# main_board-v2_2.net
KiCad netlist of a schematic drawn in EAGLE
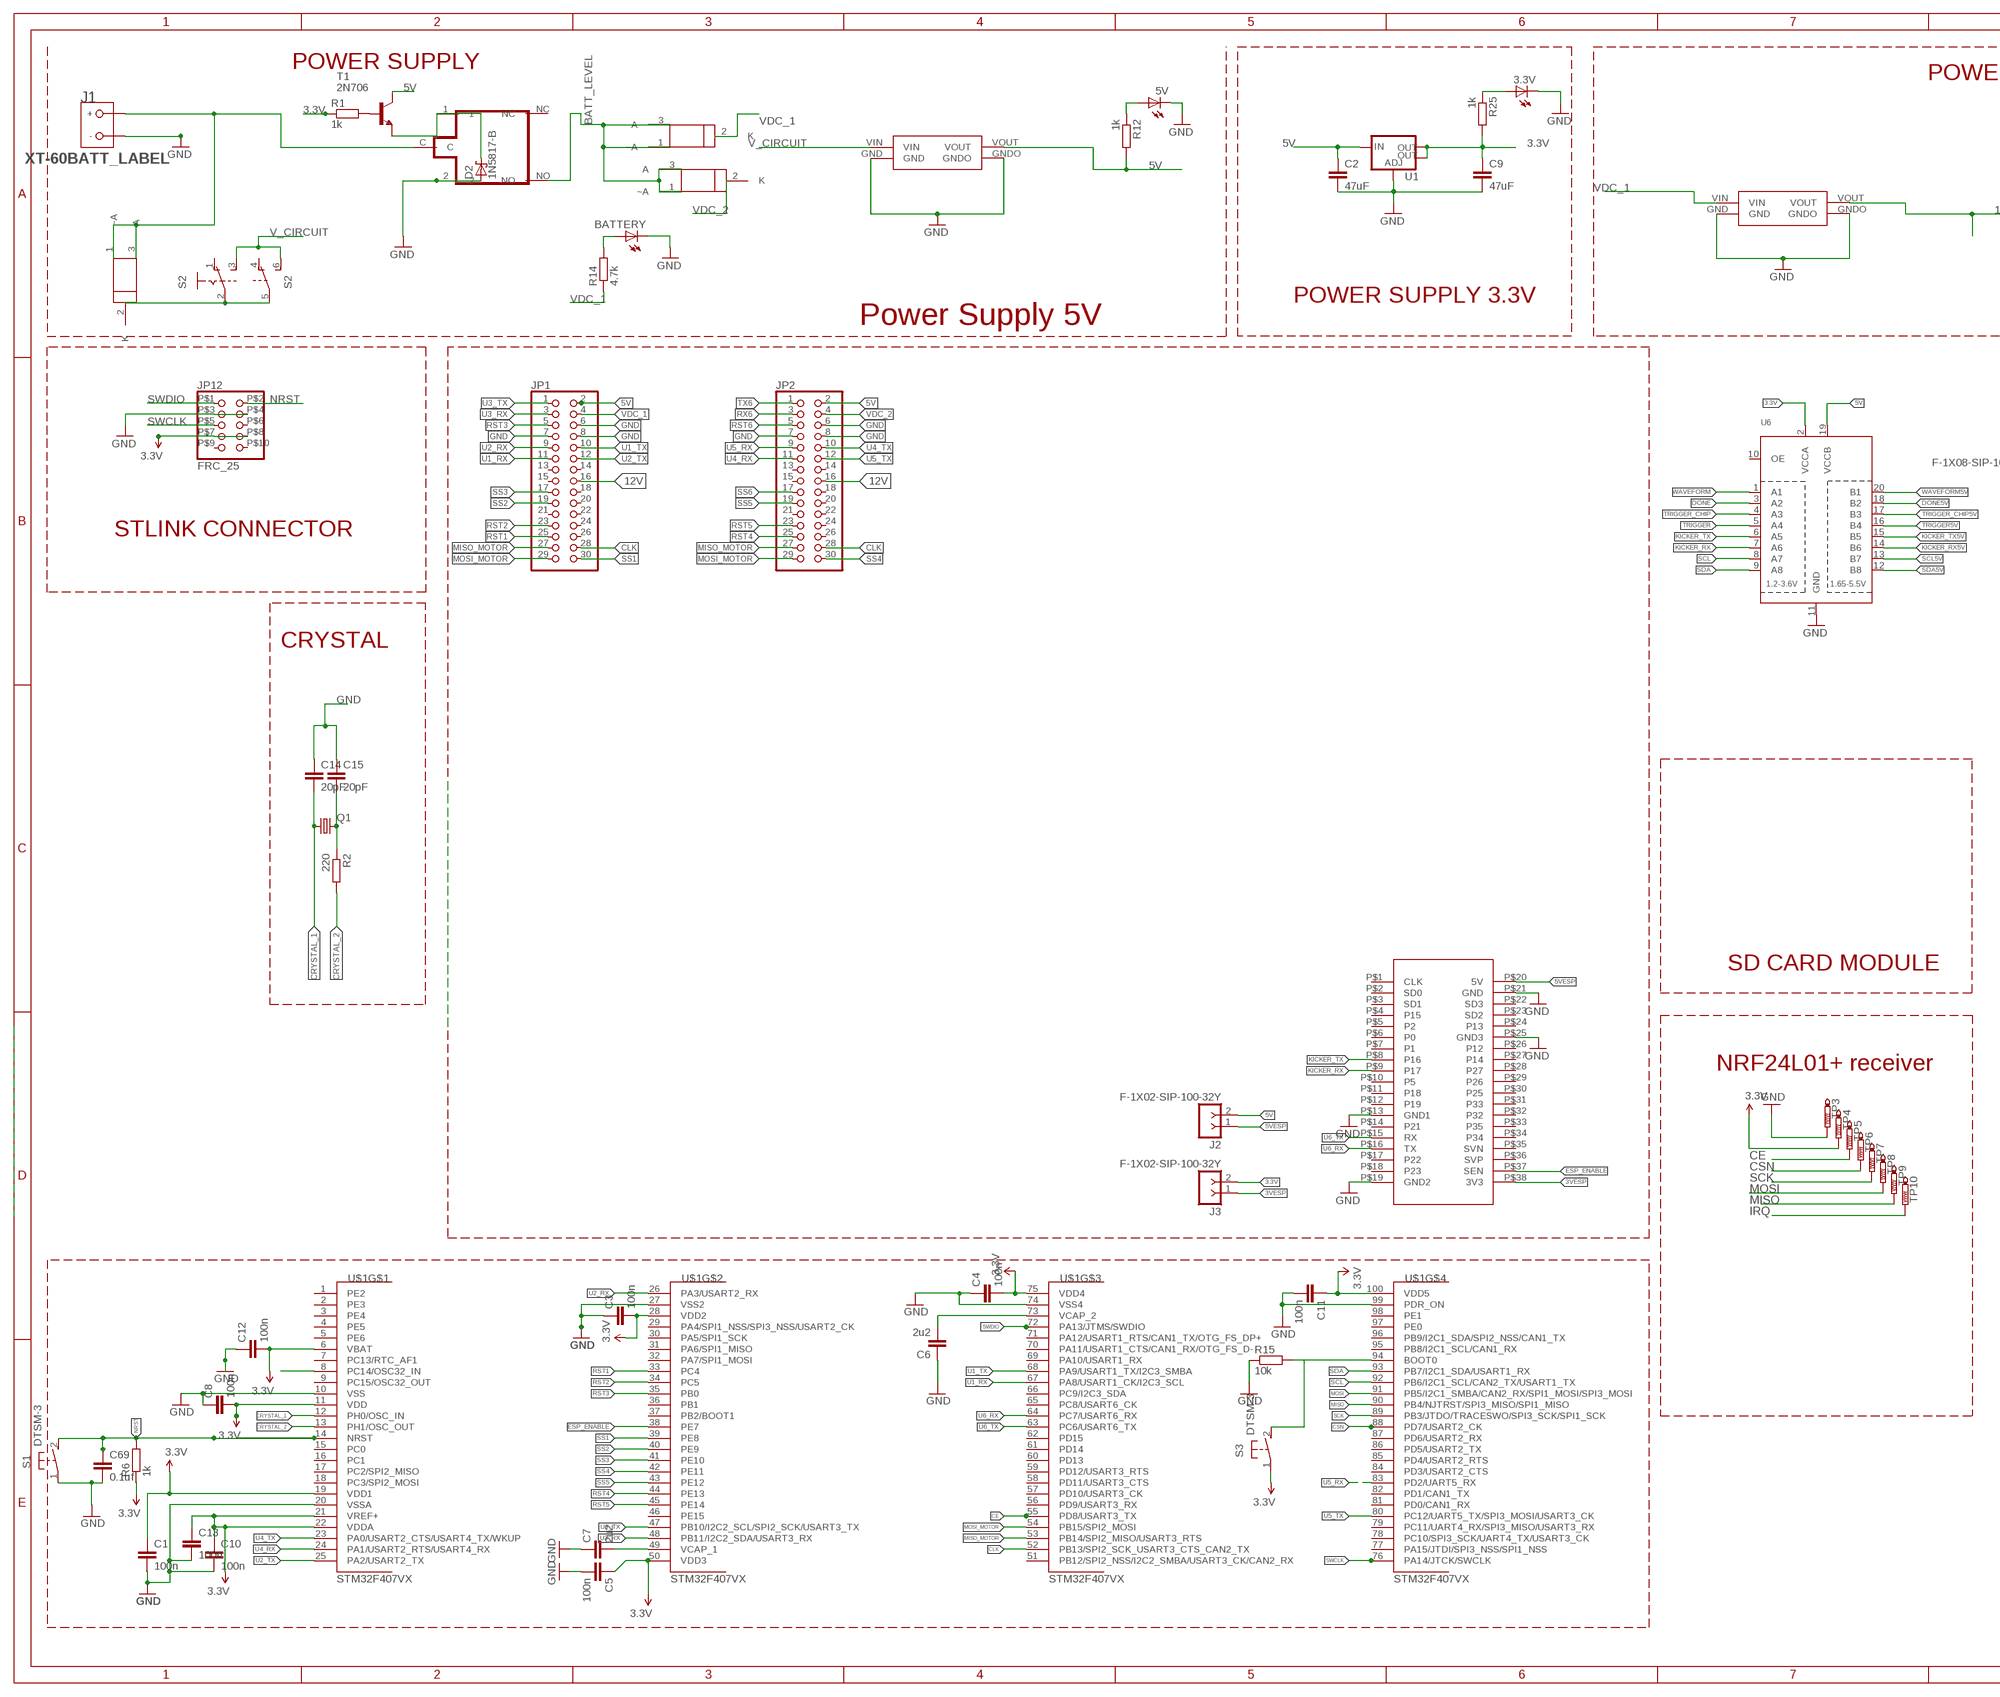
[diagram p0: schematic, sheet 1, part 1 of 2]
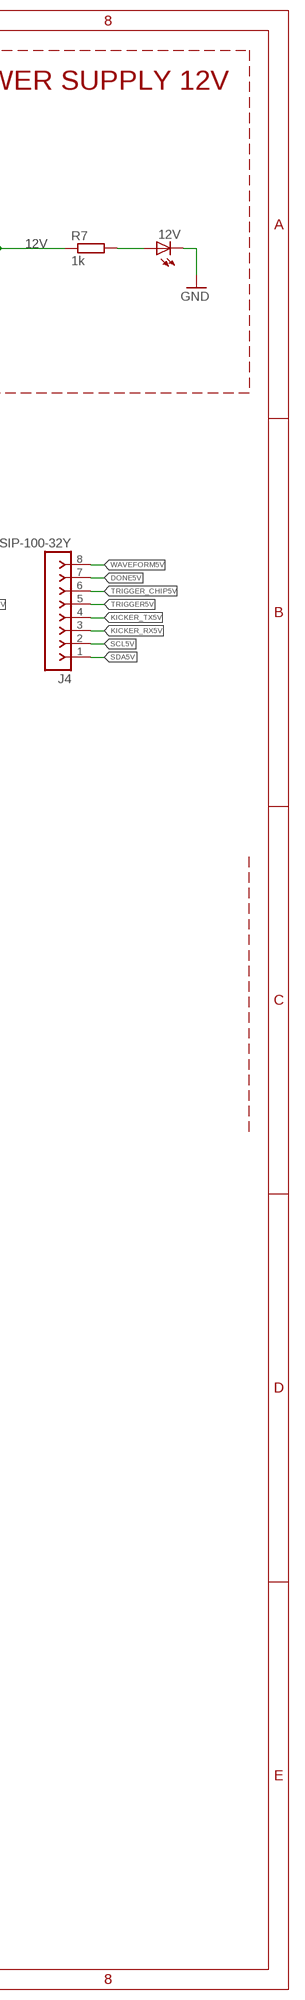
[diagram p1: schematic, sheet 1, part 2 of 2]

(export (version "E")
  (design (tool "Eeschema 10.0.6"))
  (components
    (comp (ref "3.3V")
      (value "LEDCHIPLED_0805")
      (footprint "eagle-import:CHIPLED_0805")
      (libsource (lib "eagle-import") (part "LEDCHIPLED_0805"))
    )
    (comp (ref "5V")
      (value "LEDCHIPLED_0805")
      (footprint "eagle-import:CHIPLED_0805")
      (libsource (lib "eagle-import") (part "LEDCHIPLED_0805"))
    )
    (comp (ref "12V")
      (value "LEDCHIPLED_0805")
      (footprint "eagle-import:CHIPLED_0805")
      (libsource (lib "eagle-import") (part "LEDCHIPLED_0805"))
    )
    (comp (ref "BATTERY")
      (value "LEDCHIPLED_0805")
      (footprint "eagle-import:CHIPLED_0805")
      (libsource (lib "eagle-import") (part "LEDCHIPLED_0805"))
    )
    (comp (ref "C1")
      (value "100n")
      (footprint "eagle-import:C1206")
      (libsource (lib "eagle-import") (part "C-EUC1206"))
    )
    (comp (ref "C2")
      (value "47uF")
      (footprint "eagle-import:C1206")
      (libsource (lib "eagle-import") (part "C-EUC1206"))
    )
    (comp (ref "C3")
      (value "100n")
      (footprint "eagle-import:C1206")
      (libsource (lib "eagle-import") (part "C-EUC1206"))
    )
    (comp (ref "C4")
      (value "100n")
      (footprint "eagle-import:C1206")
      (libsource (lib "eagle-import") (part "C-EUC1206"))
    )
    (comp (ref "C5")
      (value "100n")
      (footprint "eagle-import:C1206")
      (libsource (lib "eagle-import") (part "C-EUC1206"))
    )
    (comp (ref "C6")
      (value "2u2")
      (footprint "eagle-import:C1206")
      (libsource (lib "eagle-import") (part "C-EUC1206"))
    )
    (comp (ref "C7")
      (value "2u2")
      (footprint "eagle-import:C1206")
      (libsource (lib "eagle-import") (part "C-EUC1206"))
    )
    (comp (ref "C8")
      (value "100n")
      (footprint "eagle-import:C1206")
      (libsource (lib "eagle-import") (part "C-EUC1206"))
    )
    (comp (ref "C9")
      (value "47uF")
      (footprint "eagle-import:C1206")
      (libsource (lib "eagle-import") (part "C-EUC1206"))
    )
    (comp (ref "C10")
      (value "100n")
      (footprint "eagle-import:C1206")
      (libsource (lib "eagle-import") (part "C-EUC1206"))
    )
    (comp (ref "C11")
      (value "100n")
      (footprint "eagle-import:C1206")
      (libsource (lib "eagle-import") (part "C-EUC1206"))
    )
    (comp (ref "C12")
      (value "100n")
      (footprint "eagle-import:C1206")
      (libsource (lib "eagle-import") (part "C-EUC1206"))
    )
    (comp (ref "C13")
      (value "100n")
      (footprint "eagle-import:C1206")
      (libsource (lib "eagle-import") (part "C-EUC1206"))
    )
    (comp (ref "C14")
      (value "20pF")
      (footprint "eagle-import:C1206")
      (libsource (lib "eagle-import") (part "C-EUC1206"))
    )
    (comp (ref "C15")
      (value "20pF")
      (footprint "eagle-import:C1206")
      (libsource (lib "eagle-import") (part "C-EUC1206"))
    )
    (comp (ref "C69")
      (value "0.1uf")
      (footprint "eagle-import:C1206")
      (libsource (lib "eagle-import") (part "C-EUC1206"))
    )
    (comp (ref "D2")
      (value "1N5817-B")
      (footprint "eagle-import:DO41-7.6")
      (libsource (lib "eagle-import") (part "1N5817-B"))
    )
    (comp (ref "J1")
      (value "XT-60BATT_LABEL")
      (footprint "eagle-import:XT-60")
      (libsource (lib "eagle-import") (part "XT-60BATT_LABEL"))
    )
    (comp (ref "J2")
      (value "F-1X02-SIP-100-32Y")
      (footprint "eagle-import:SIP-100-02-32Y")
      (libsource (lib "eagle-import") (part "F-1X02-SIP-100-32Y"))
    )
    (comp (ref "J3")
      (value "F-1X02-SIP-100-32Y")
      (footprint "eagle-import:SIP-100-02-32Y")
      (libsource (lib "eagle-import") (part "F-1X02-SIP-100-32Y"))
    )
    (comp (ref "J4")
      (value "F-1X08-SIP-100-32Y")
      (footprint "eagle-import:SIP-100-08-32Y")
      (libsource (lib "eagle-import") (part "F-1X08-SIP-100-32Y"))
    )
    (comp (ref "JP1")
      (value "PINHD-2X15_2.54")
      (footprint "eagle-import:2X15")
      (libsource (lib "eagle-import") (part "PINHD-2X15_2.54"))
    )
    (comp (ref "JP2")
      (value "PINHD-2X15_2.54")
      (footprint "eagle-import:2X15")
      (libsource (lib "eagle-import") (part "PINHD-2X15_2.54"))
    )
    (comp (ref "JP12")
      (value "FRC_25")
      (footprint "eagle-import:FRC2_5")
      (libsource (lib "eagle-import") (part "FRC_25"))
    )
    (comp (ref "Q1")
      (value "CRYSTALHC49U-V")
      (footprint "eagle-import:HC49U-V")
      (libsource (lib "eagle-import") (part "CRYSTALHC49U-V"))
    )
    (comp (ref "R1")
      (value "1k")
      (footprint "eagle-import:R1206")
      (libsource (lib "eagle-import") (part "R-EU_R1206"))
    )
    (comp (ref "R2")
      (value "220")
      (footprint "eagle-import:R1206")
      (libsource (lib "eagle-import") (part "R-EU_R1206"))
    )
    (comp (ref "R6")
      (value "1k")
      (footprint "eagle-import:R1206")
      (libsource (lib "eagle-import") (part "R-EU_R1206"))
    )
    (comp (ref "R7")
      (value "1k")
      (footprint "eagle-import:R1206")
      (libsource (lib "eagle-import") (part "R-EU_R1206"))
    )
    (comp (ref "R12")
      (value "1k")
      (footprint "eagle-import:R1206")
      (libsource (lib "eagle-import") (part "R-EU_R1206"))
    )
    (comp (ref "R14")
      (value "4.7k")
      (footprint "eagle-import:R1206")
      (libsource (lib "eagle-import") (part "R-EU_R1206"))
    )
    (comp (ref "R15")
      (value "10k")
      (footprint "eagle-import:R1206")
      (libsource (lib "eagle-import") (part "R-EU_R1206"))
    )
    (comp (ref "R25")
      (value "1k")
      (footprint "eagle-import:R1206")
      (libsource (lib "eagle-import") (part "R-EU_R1206"))
    )
    (comp (ref "S1")
      (value "DTSM-3")
      (footprint "eagle-import:DTSM-3")
      (libsource (lib "eagle-import") (part "DTSM-3"))
    )
    (comp (ref "S2")
      (value "A68-A31")
      (footprint "eagle-import:A68-A31")
      (libsource (lib "eagle-import") (part "A68-A31"))
    )
    (comp (ref "S3")
      (value "DTSM-3")
      (footprint "eagle-import:DTSM-3")
      (libsource (lib "eagle-import") (part "DTSM-3"))
    )
    (comp (ref "T1")
      (value "2N706")
      (footprint "eagle-import:TO18")
      (libsource (lib "eagle-import") (part "2N706"))
    )
    (comp (ref "TP3")
      (value "PTR1PAD1-13")
      (footprint "eagle-import:P1-13")
      (libsource (lib "eagle-import") (part "PTR1PAD1-13"))
    )
    (comp (ref "TP4")
      (value "PTR1PAD1-13")
      (footprint "eagle-import:P1-13")
      (libsource (lib "eagle-import") (part "PTR1PAD1-13"))
    )
    (comp (ref "TP5")
      (value "PTR1PAD1-13")
      (footprint "eagle-import:P1-13")
      (libsource (lib "eagle-import") (part "PTR1PAD1-13"))
    )
    (comp (ref "TP6")
      (value "PTR1PAD1-13")
      (footprint "eagle-import:P1-13")
      (libsource (lib "eagle-import") (part "PTR1PAD1-13"))
    )
    (comp (ref "TP7")
      (value "PTR1PAD1-13")
      (footprint "eagle-import:P1-13")
      (libsource (lib "eagle-import") (part "PTR1PAD1-13"))
    )
    (comp (ref "TP8")
      (value "PTR1PAD1-13")
      (footprint "eagle-import:P1-13")
      (libsource (lib "eagle-import") (part "PTR1PAD1-13"))
    )
    (comp (ref "TP9")
      (value "PTR1PAD1-13")
      (footprint "eagle-import:P1-13")
      (libsource (lib "eagle-import") (part "PTR1PAD1-13"))
    )
    (comp (ref "TP10")
      (value "PTR1PAD1-13")
      (footprint "eagle-import:P1-13")
      (libsource (lib "eagle-import") (part "PTR1PAD1-13"))
    )
    (comp (ref "U$1")
      (value "STM32F407VX")
      (footprint "eagle-import:LQFP100")
      (libsource (lib "eagle-import") (part "STM32F407VX"))
    )
    (comp (ref "U$2")
      (value "REL")
      (footprint "eagle-import:REL")
      (libsource (lib "eagle-import") (part "REL"))
    )
    (comp (ref "U$3")
      (value "BUCK")
      (footprint "eagle-import:BUCK")
      (libsource (lib "eagle-import") (part "BUCK"))
    )
    (comp (ref "U$4")
      (value "BUCK")
      (footprint "eagle-import:BUCK")
      (libsource (lib "eagle-import") (part "BUCK"))
    )
    (comp (ref "U$6")
      (value "NODEMCU32S")
      (footprint "eagle-import:NODEMCU32")
      (libsource (lib "eagle-import") (part "NODEMCU32S"))
    )
    (comp (ref "U1")
      (value "V_REG_LM1117SOT223")
      (footprint "eagle-import:SOT223")
      (libsource (lib "eagle-import") (part "V_REG_LM1117SOT223"))
    )
    (comp (ref "U2")
      (value "LP38690DT-3.3")
      (footprint "eagle-import:TO228P1042X238-3N")
      (libsource (lib "eagle-import") (part "LP38690DT-3.3"))
    )
    (comp (ref "U3")
      (value "LP38690DT-3.3")
      (footprint "eagle-import:TO228P1042X238-3N")
      (libsource (lib "eagle-import") (part "LP38690DT-3.3"))
    )
    (comp (ref "U4")
      (value "LP38690DT-3.3")
      (footprint "eagle-import:TO228P1042X238-3N")
      (libsource (lib "eagle-import") (part "LP38690DT-3.3"))
    )
    (comp (ref "U6")
      (value "TXB0108PWR")
      (footprint "eagle-import:TSSOP20")
      (libsource (lib "eagle-import") (part "TXB0108PWR"))
    )
  )
  (nets
    (net (code "1") (name "/BATT_LEVEL") (class "Default")
      (node (ref "U$2") (pin "NO") (pinfunction "NO_NO") (pintype "bidirectional"))
      (node (ref "U2") (pin "1") (pinfunction "~{A}_1") (pintype "bidirectional"))
      (node (ref "U2") (pin "3") (pinfunction "A_3") (pintype "bidirectional"))
      (node (ref "U4") (pin "1") (pinfunction "~{A}_1") (pintype "bidirectional"))
      (node (ref "U4") (pin "3") (pinfunction "A_3") (pintype "bidirectional"))
    )
    (net (code "2") (name "/IRQ") (class "Default")
      (node (ref "TP10") (pin "TP") (pinfunction "TP_TP") (pintype "input"))
    )
    (net (code "3") (name "/V_CIRCUIT") (class "Default")
      (node (ref "S2") (pin "3") (pinfunction "S_3") (pintype "passive"))
      (node (ref "S2") (pin "6") (pinfunction "S_6") (pintype "passive"))
      (node (ref "U$3") (pin "VIN") (pinfunction "VIN_VIN") (pintype "bidirectional"))
    )
    (net (code "4") (name "3.3V") (class "Default")
      (node (ref "C1") (pin "1") (pinfunction "1_1") (pintype "passive"))
      (node (ref "C10") (pin "1") (pinfunction "1_1") (pintype "passive"))
      (node (ref "C11") (pin "1") (pinfunction "1_1") (pintype "passive"))
      (node (ref "C12") (pin "2") (pinfunction "2_2") (pintype "passive"))
      (node (ref "C13") (pin "1") (pinfunction "1_1") (pintype "passive"))
      (node (ref "C3") (pin "2") (pinfunction "2_2") (pintype "passive"))
      (node (ref "C4") (pin "2") (pinfunction "2_2") (pintype "passive"))
      (node (ref "C5") (pin "1") (pinfunction "1_1") (pintype "passive"))
      (node (ref "C8") (pin "2") (pinfunction "2_2") (pintype "passive"))
      (node (ref "C9") (pin "1") (pinfunction "1_1") (pintype "passive"))
      (node (ref "J3") (pin "2") (pinfunction "2_2") (pintype "passive"))
      (node (ref "JP12") (pin "P$7") (pinfunction "7_P$7") (pintype "passive"))
      (node (ref "JP12") (pin "P$8") (pinfunction "8_P$8") (pintype "passive"))
      (node (ref "R1") (pin "1") (pinfunction "1_1") (pintype "passive"))
      (node (ref "R25") (pin "2") (pinfunction "2_2") (pintype "passive"))
      (node (ref "R6") (pin "1") (pinfunction "1_1") (pintype "passive"))
      (node (ref "S3") (pin "1") (pinfunction "1_1") (pintype "passive"))
      (node (ref "TP4") (pin "TP") (pinfunction "TP_TP") (pintype "input"))
      (node (ref "U$1") (pin "100") (pinfunction "VDD5_100") (pintype "bidirectional"))
      (node (ref "U$1") (pin "11") (pinfunction "VDD_11") (pintype "bidirectional"))
      (node (ref "U$1") (pin "19") (pinfunction "VDD1_19") (pintype "bidirectional"))
      (node (ref "U$1") (pin "21") (pinfunction "VREF+_21") (pintype "bidirectional"))
      (node (ref "U$1") (pin "22") (pinfunction "VDDA_22") (pintype "bidirectional"))
      (node (ref "U$1") (pin "28") (pinfunction "VDD2_28") (pintype "bidirectional"))
      (node (ref "U$1") (pin "50") (pinfunction "VDD3_50") (pintype "bidirectional"))
      (node (ref "U$1") (pin "6") (pinfunction "VBAT_6") (pintype "bidirectional"))
      (node (ref "U$1") (pin "75") (pinfunction "VDD4_75") (pintype "bidirectional"))
      (node (ref "U1") (pin "2") (pinfunction "OUT_2") (pintype "output"))
      (node (ref "U1") (pin "4") (pinfunction "OUT_4") (pintype "output"))
      (node (ref "U6") (pin "2") (pinfunction "VCCA_2") (pintype "bidirectional"))
    )
    (net (code "5") (name "3VESP") (class "Default")
      (node (ref "J3") (pin "1") (pinfunction "1_1") (pintype "passive"))
      (node (ref "U$6") (pin "P$38") (pinfunction "3V3_P$38") (pintype "bidirectional"))
    )
    (net (code "6") (name "5V") (class "Default")
      (node (ref "C2") (pin "1") (pinfunction "1_1") (pintype "passive"))
      (node (ref "J2") (pin "2") (pinfunction "2_2") (pintype "passive"))
      (node (ref "JP1") (pin "2") (pinfunction "2_2") (pintype "passive"))
      (node (ref "JP2") (pin "2") (pinfunction "2_2") (pintype "passive"))
      (node (ref "R12") (pin "2") (pinfunction "2_2") (pintype "passive"))
      (node (ref "T1") (pin "3") (pinfunction "C_3") (pintype "passive"))
      (node (ref "U$3") (pin "VOUT") (pinfunction "VOUT_VOUT") (pintype "bidirectional"))
      (node (ref "U1") (pin "3") (pinfunction "IN_3") (pintype "input"))
      (node (ref "U6") (pin "19") (pinfunction "VCCB_19") (pintype "bidirectional"))
    )
    (net (code "7") (name "5VESP") (class "Default")
      (node (ref "J2") (pin "1") (pinfunction "1_1") (pintype "passive"))
      (node (ref "U$6") (pin "P$20") (pinfunction "5V_P$20") (pintype "bidirectional"))
    )
    (net (code "8") (name "12V") (class "Default")
      (node (ref "JP1") (pin "16") (pinfunction "16_16") (pintype "passive"))
      (node (ref "JP2") (pin "16") (pinfunction "16_16") (pintype "passive"))
      (node (ref "R7") (pin "1") (pinfunction "1_1") (pintype "passive"))
      (node (ref "U$4") (pin "VOUT") (pinfunction "VOUT_VOUT") (pintype "bidirectional"))
    )
    (net (code "9") (name "CE") (class "Default")
      (node (ref "TP5") (pin "TP") (pinfunction "TP_TP") (pintype "input"))
      (node (ref "U$1") (pin "55") (pinfunction "PD8/USART3_TX_55") (pintype "bidirectional"))
    )
    (net (code "10") (name "CLK") (class "Default")
      (node (ref "JP1") (pin "28") (pinfunction "28_28") (pintype "passive"))
      (node (ref "JP2") (pin "28") (pinfunction "28_28") (pintype "passive"))
      (node (ref "U$1") (pin "52") (pinfunction "PB13/SPI2_SCK_USART3_CTS_CAN2_TX_52") (pintype "bidirectional"))
    )
    (net (code "11") (name "CRYSTAL_1") (class "Default")
      (node (ref "C14") (pin "2") (pinfunction "2_2") (pintype "passive"))
      (node (ref "Q1") (pin "1") (pinfunction "1_1") (pintype "passive"))
      (node (ref "U$1") (pin "12") (pinfunction "PH0/OSC_IN_12") (pintype "bidirectional"))
    )
    (net (code "12") (name "CRYSTAL_2") (class "Default")
      (node (ref "R2") (pin "2") (pinfunction "2_2") (pintype "passive"))
      (node (ref "U$1") (pin "13") (pinfunction "PH1/OSC_OUT_13") (pintype "bidirectional"))
    )
    (net (code "13") (name "CSN") (class "Default")
      (node (ref "TP6") (pin "TP") (pinfunction "TP_TP") (pintype "input"))
      (node (ref "U$1") (pin "88") (pinfunction "PD7/USART2_CK_88") (pintype "bidirectional"))
    )
    (net (code "14") (name "DONE") (class "Default")
      (node (ref "U6") (pin "3") (pinfunction "A2_3") (pintype "bidirectional"))
    )
    (net (code "15") (name "DONE5V") (class "Default")
      (node (ref "J4") (pin "7") (pinfunction "7_7") (pintype "passive"))
      (node (ref "U6") (pin "18") (pinfunction "B2_18") (pintype "bidirectional"))
    )
    (net (code "16") (name "ESP_ENABLE") (class "Default")
      (node (ref "U$1") (pin "38") (pinfunction "PE7_38") (pintype "bidirectional"))
      (node (ref "U$6") (pin "P$37") (pinfunction "SEN_P$37") (pintype "bidirectional"))
    )
    (net (code "17") (name "GND") (class "Default")
      (node (ref "12V") (pin "C") (pinfunction "C_C") (pintype "passive"))
      (node (ref "3.3V") (pin "C") (pinfunction "C_C") (pintype "passive"))
      (node (ref "5V") (pin "C") (pinfunction "C_C") (pintype "passive"))
      (node (ref "BATTERY") (pin "C") (pinfunction "C_C") (pintype "passive"))
      (node (ref "C1") (pin "2") (pinfunction "2_2") (pintype "passive"))
      (node (ref "C10") (pin "2") (pinfunction "2_2") (pintype "passive"))
      (node (ref "C11") (pin "2") (pinfunction "2_2") (pintype "passive"))
      (node (ref "C12") (pin "1") (pinfunction "1_1") (pintype "passive"))
      (node (ref "C13") (pin "2") (pinfunction "2_2") (pintype "passive"))
      (node (ref "C14") (pin "1") (pinfunction "1_1") (pintype "passive"))
      (node (ref "C15") (pin "1") (pinfunction "1_1") (pintype "passive"))
      (node (ref "C2") (pin "2") (pinfunction "2_2") (pintype "passive"))
      (node (ref "C3") (pin "1") (pinfunction "1_1") (pintype "passive"))
      (node (ref "C4") (pin "1") (pinfunction "1_1") (pintype "passive"))
      (node (ref "C5") (pin "2") (pinfunction "2_2") (pintype "passive"))
      (node (ref "C6") (pin "1") (pinfunction "1_1") (pintype "passive"))
      (node (ref "C69") (pin "2") (pinfunction "2_2") (pintype "passive"))
      (node (ref "C7") (pin "1") (pinfunction "1_1") (pintype "passive"))
      (node (ref "C8") (pin "1") (pinfunction "1_1") (pintype "passive"))
      (node (ref "C9") (pin "2") (pinfunction "2_2") (pintype "passive"))
      (node (ref "D2") (pin "A") (pinfunction "A_A") (pintype "passive"))
      (node (ref "J1") (pin "GND") (pinfunction "-_GND") (pintype "passive"))
      (node (ref "JP1") (pin "6") (pinfunction "6_6") (pintype "passive"))
      (node (ref "JP1") (pin "7") (pinfunction "7_7") (pintype "passive"))
      (node (ref "JP1") (pin "8") (pinfunction "8_8") (pintype "passive"))
      (node (ref "JP12") (pin "P$3") (pinfunction "3_P$3") (pintype "passive"))
      (node (ref "JP12") (pin "P$4") (pinfunction "4_P$4") (pintype "passive"))
      (node (ref "JP2") (pin "6") (pinfunction "6_6") (pintype "passive"))
      (node (ref "JP2") (pin "7") (pinfunction "7_7") (pintype "passive"))
      (node (ref "JP2") (pin "8") (pinfunction "8_8") (pintype "passive"))
      (node (ref "R15") (pin "1") (pinfunction "1_1") (pintype "passive"))
      (node (ref "S1") (pin "1") (pinfunction "1_1") (pintype "passive"))
      (node (ref "TP3") (pin "TP") (pinfunction "TP_TP") (pintype "input"))
      (node (ref "U$1") (pin "10") (pinfunction "VSS_10") (pintype "bidirectional"))
      (node (ref "U$1") (pin "20") (pinfunction "VSSA_20") (pintype "bidirectional"))
      (node (ref "U$1") (pin "27") (pinfunction "VSS2_27") (pintype "bidirectional"))
      (node (ref "U$1") (pin "74") (pinfunction "VSS4_74") (pintype "bidirectional"))
      (node (ref "U$1") (pin "99") (pinfunction "PDR_ON_99") (pintype "bidirectional"))
      (node (ref "U$2") (pin "2") (pinfunction "2_2") (pintype "bidirectional"))
      (node (ref "U$3") (pin "GND") (pinfunction "GND_GND") (pintype "bidirectional"))
      (node (ref "U$3") (pin "GNDO") (pinfunction "GNDO_GNDO") (pintype "bidirectional"))
      (node (ref "U$4") (pin "GND") (pinfunction "GND_GND") (pintype "bidirectional"))
      (node (ref "U$4") (pin "GNDO") (pinfunction "GNDO_GNDO") (pintype "bidirectional"))
      (node (ref "U$6") (pin "P$13") (pinfunction "GND1_P$13") (pintype "bidirectional"))
      (node (ref "U$6") (pin "P$19") (pinfunction "GND2_P$19") (pintype "bidirectional"))
      (node (ref "U$6") (pin "P$21") (pinfunction "GND_P$21") (pintype "bidirectional"))
      (node (ref "U$6") (pin "P$25") (pinfunction "GND3_P$25") (pintype "bidirectional"))
      (node (ref "U1") (pin "1") (pinfunction "ADJ_1") (pintype "input"))
      (node (ref "U6") (pin "11") (pinfunction "GND_11") (pintype "bidirectional"))
    )
    (net (code "18") (name "KICKER_RX") (class "Default")
      (node (ref "U$6") (pin "P$9") (pinfunction "P17_P$9") (pintype "bidirectional"))
      (node (ref "U6") (pin "7") (pinfunction "A6_7") (pintype "bidirectional"))
    )
    (net (code "19") (name "KICKER_RX5V") (class "Default")
      (node (ref "J4") (pin "3") (pinfunction "3_3") (pintype "passive"))
      (node (ref "U6") (pin "14") (pinfunction "B6_14") (pintype "bidirectional"))
    )
    (net (code "20") (name "KICKER_TX") (class "Default")
      (node (ref "U$6") (pin "P$8") (pinfunction "P16_P$8") (pintype "bidirectional"))
      (node (ref "U6") (pin "6") (pinfunction "A5_6") (pintype "bidirectional"))
    )
    (net (code "21") (name "KICKER_TX5V") (class "Default")
      (node (ref "J4") (pin "4") (pinfunction "4_4") (pintype "passive"))
      (node (ref "U6") (pin "15") (pinfunction "B5_15") (pintype "bidirectional"))
    )
    (net (code "22") (name "MISO") (class "Default")
      (node (ref "TP9") (pin "TP") (pinfunction "TP_TP") (pintype "input"))
      (node (ref "U$1") (pin "90") (pinfunction "PB4/NJTRST/SPI3_MISO/SPI1_MISO_90") (pintype "bidirectional"))
    )
    (net (code "23") (name "MISO_MOTOR") (class "Default")
      (node (ref "JP1") (pin "27") (pinfunction "27_27") (pintype "passive"))
      (node (ref "JP2") (pin "27") (pinfunction "27_27") (pintype "passive"))
      (node (ref "U$1") (pin "53") (pinfunction "PB14/SPI2_MISO/USART3_RTS_53") (pintype "bidirectional"))
    )
    (net (code "24") (name "MOSI") (class "Default")
      (node (ref "TP8") (pin "TP") (pinfunction "TP_TP") (pintype "input"))
      (node (ref "U$1") (pin "91") (pinfunction "PB5/I2C1_SMBA/CAN2_RX/SPI1_MOSI/SPI3_MOSI_91") (pintype "bidirectional"))
    )
    (net (code "25") (name "MOSI_MOTOR") (class "Default")
      (node (ref "JP1") (pin "29") (pinfunction "29_29") (pintype "passive"))
      (node (ref "JP2") (pin "29") (pinfunction "29_29") (pintype "passive"))
      (node (ref "U$1") (pin "54") (pinfunction "PB15/SPI2_MOSI_54") (pintype "bidirectional"))
    )
    (net (code "26") (name "NRST") (class "Default")
      (node (ref "C69") (pin "1") (pinfunction "1_1") (pintype "passive"))
      (node (ref "JP12") (pin "P$2") (pinfunction "2_P$2") (pintype "passive"))
      (node (ref "R6") (pin "2") (pinfunction "2_2") (pintype "passive"))
      (node (ref "S1") (pin "2") (pinfunction "2_2") (pintype "passive"))
      (node (ref "U$1") (pin "14") (pinfunction "NRST_14") (pintype "bidirectional"))
    )
    (net (code "27") (name "Net-(3.3V-PadA)") (class "Default")
      (node (ref "3.3V") (pin "A") (pinfunction "A_A") (pintype "passive"))
      (node (ref "R25") (pin "1") (pinfunction "1_1") (pintype "passive"))
    )
    (net (code "28") (name "Net-(5V-PadA)") (class "Default")
      (node (ref "5V") (pin "A") (pinfunction "A_A") (pintype "passive"))
      (node (ref "R12") (pin "1") (pinfunction "1_1") (pintype "passive"))
    )
    (net (code "29") (name "Net-(12V-PadA)") (class "Default")
      (node (ref "12V") (pin "A") (pinfunction "A_A") (pintype "passive"))
      (node (ref "R7") (pin "2") (pinfunction "2_2") (pintype "passive"))
    )
    (net (code "30") (name "Net-(BATTERY-PadA)") (class "Default")
      (node (ref "BATTERY") (pin "A") (pinfunction "A_A") (pintype "passive"))
      (node (ref "R14") (pin "2") (pinfunction "2_2") (pintype "passive"))
    )
    (net (code "31") (name "Net-(C15-Pad2)") (class "Default")
      (node (ref "C15") (pin "2") (pinfunction "2_2") (pintype "passive"))
      (node (ref "Q1") (pin "2") (pinfunction "2_2") (pintype "passive"))
      (node (ref "R2") (pin "1") (pinfunction "1_1") (pintype "passive"))
    )
    (net (code "32") (name "Net-(J1-+)") (class "Default")
      (node (ref "J1") (pin "BATT") (pinfunction "+_BATT") (pintype "passive"))
      (node (ref "U$2") (pin "C") (pinfunction "C_C") (pintype "bidirectional"))
      (node (ref "U3") (pin "1") (pinfunction "~{A}_1") (pintype "bidirectional"))
      (node (ref "U3") (pin "3") (pinfunction "A_3") (pintype "bidirectional"))
    )
    (net (code "33") (name "Net-(S2A-P)") (class "Default")
      (node (ref "S2") (pin "2") (pinfunction "P_2") (pintype "passive"))
      (node (ref "S2") (pin "5") (pinfunction "P_5") (pintype "passive"))
      (node (ref "U3") (pin "2") (pinfunction "K_2") (pintype "bidirectional"))
    )
    (net (code "34") (name "Net-(T1-B)") (class "Default")
      (node (ref "R1") (pin "2") (pinfunction "2_2") (pintype "passive"))
      (node (ref "T1") (pin "2") (pinfunction "B_2") (pintype "passive"))
    )
    (net (code "35") (name "Net-(T1-E)") (class "Default")
      (node (ref "D2") (pin "C") (pinfunction "C_C") (pintype "passive"))
      (node (ref "T1") (pin "1") (pinfunction "E_1") (pintype "passive"))
      (node (ref "U$2") (pin "1") (pinfunction "1_1") (pintype "bidirectional"))
    )
    (net (code "36") (name "Net-(U$1B-VCAP_1)") (class "Default")
      (node (ref "C7") (pin "2") (pinfunction "2_2") (pintype "passive"))
      (node (ref "U$1") (pin "49") (pinfunction "VCAP_1_49") (pintype "bidirectional"))
    )
    (net (code "37") (name "Net-(U$1C-VCAP_2)") (class "Default")
      (node (ref "C6") (pin "2") (pinfunction "2_2") (pintype "passive"))
      (node (ref "U$1") (pin "73") (pinfunction "VCAP_2_73") (pintype "bidirectional"))
    )
    (net (code "38") (name "Net-(U$1D-BOOT0)") (class "Default")
      (node (ref "R15") (pin "2") (pinfunction "2_2") (pintype "passive"))
      (node (ref "S3") (pin "2") (pinfunction "2_2") (pintype "passive"))
      (node (ref "U$1") (pin "94") (pinfunction "BOOT0_94") (pintype "bidirectional"))
    )
    (net (code "39") (name "RST1") (class "Default")
      (node (ref "JP1") (pin "25") (pinfunction "25_25") (pintype "passive"))
      (node (ref "U$1") (pin "33") (pinfunction "PC4_33") (pintype "bidirectional"))
    )
    (net (code "40") (name "RST2") (class "Default")
      (node (ref "JP1") (pin "23") (pinfunction "23_23") (pintype "passive"))
      (node (ref "U$1") (pin "34") (pinfunction "PC5_34") (pintype "bidirectional"))
    )
    (net (code "41") (name "RST3") (class "Default")
      (node (ref "JP1") (pin "5") (pinfunction "5_5") (pintype "passive"))
      (node (ref "U$1") (pin "35") (pinfunction "PB0_35") (pintype "bidirectional"))
    )
    (net (code "42") (name "RST4") (class "Default")
      (node (ref "JP2") (pin "25") (pinfunction "25_25") (pintype "passive"))
      (node (ref "U$1") (pin "44") (pinfunction "PE13_44") (pintype "bidirectional"))
    )
    (net (code "43") (name "RST5") (class "Default")
      (node (ref "JP2") (pin "23") (pinfunction "23_23") (pintype "passive"))
      (node (ref "U$1") (pin "45") (pinfunction "PE14_45") (pintype "bidirectional"))
    )
    (net (code "44") (name "RST6") (class "Default")
      (node (ref "JP2") (pin "5") (pinfunction "5_5") (pintype "passive"))
    )
    (net (code "45") (name "RX6") (class "Default")
      (node (ref "JP2") (pin "3") (pinfunction "3_3") (pintype "passive"))
    )
    (net (code "46") (name "SCK") (class "Default")
      (node (ref "TP7") (pin "TP") (pinfunction "TP_TP") (pintype "input"))
      (node (ref "U$1") (pin "89") (pinfunction "PB3/JTDO/TRACESWO/SPI3_SCK/SPI1_SCK_89") (pintype "bidirectional"))
    )
    (net (code "47") (name "SCL") (class "Default")
      (node (ref "U$1") (pin "92") (pinfunction "PB6/I2C1_SCL/CAN2_TX/USART1_TX_92") (pintype "bidirectional"))
      (node (ref "U6") (pin "8") (pinfunction "A7_8") (pintype "bidirectional"))
    )
    (net (code "48") (name "SCL5V") (class "Default")
      (node (ref "J4") (pin "2") (pinfunction "2_2") (pintype "passive"))
      (node (ref "U6") (pin "13") (pinfunction "B7_13") (pintype "bidirectional"))
    )
    (net (code "49") (name "SDA") (class "Default")
      (node (ref "U$1") (pin "93") (pinfunction "PB7/I2C1_SDA/USART1_RX_93") (pintype "bidirectional"))
      (node (ref "U6") (pin "9") (pinfunction "A8_9") (pintype "bidirectional"))
    )
    (net (code "50") (name "SDA5V") (class "Default")
      (node (ref "J4") (pin "1") (pinfunction "1_1") (pintype "passive"))
      (node (ref "U6") (pin "12") (pinfunction "B8_12") (pintype "bidirectional"))
    )
    (net (code "51") (name "SS1") (class "Default")
      (node (ref "JP1") (pin "30") (pinfunction "30_30") (pintype "passive"))
      (node (ref "U$1") (pin "39") (pinfunction "PE8_39") (pintype "bidirectional"))
    )
    (net (code "52") (name "SS2") (class "Default")
      (node (ref "JP1") (pin "19") (pinfunction "19_19") (pintype "passive"))
      (node (ref "U$1") (pin "40") (pinfunction "PE9_40") (pintype "bidirectional"))
    )
    (net (code "53") (name "SS3") (class "Default")
      (node (ref "JP1") (pin "17") (pinfunction "17_17") (pintype "passive"))
      (node (ref "U$1") (pin "41") (pinfunction "PE10_41") (pintype "bidirectional"))
    )
    (net (code "54") (name "SS4") (class "Default")
      (node (ref "JP2") (pin "30") (pinfunction "30_30") (pintype "passive"))
      (node (ref "U$1") (pin "42") (pinfunction "PE11_42") (pintype "bidirectional"))
    )
    (net (code "55") (name "SS5") (class "Default")
      (node (ref "JP2") (pin "19") (pinfunction "19_19") (pintype "passive"))
      (node (ref "U$1") (pin "43") (pinfunction "PE12_43") (pintype "bidirectional"))
    )
    (net (code "56") (name "SS6") (class "Default")
      (node (ref "JP2") (pin "17") (pinfunction "17_17") (pintype "passive"))
    )
    (net (code "57") (name "SWCLK") (class "Default")
      (node (ref "JP12") (pin "P$5") (pinfunction "5_P$5") (pintype "passive"))
      (node (ref "U$1") (pin "76") (pinfunction "PA14/JTCK/SWCLK_76") (pintype "bidirectional"))
    )
    (net (code "58") (name "SWDIO") (class "Default")
      (node (ref "JP12") (pin "P$1") (pinfunction "1_P$1") (pintype "passive"))
      (node (ref "U$1") (pin "72") (pinfunction "PA13/JTMS/SWDIO_72") (pintype "bidirectional"))
    )
    (net (code "59") (name "TRIGGER") (class "Default")
      (node (ref "U6") (pin "5") (pinfunction "A4_5") (pintype "bidirectional"))
    )
    (net (code "60") (name "TRIGGER5V") (class "Default")
      (node (ref "J4") (pin "5") (pinfunction "5_5") (pintype "passive"))
      (node (ref "U6") (pin "16") (pinfunction "B4_16") (pintype "bidirectional"))
    )
    (net (code "61") (name "TRIGGER_CHIP") (class "Default")
      (node (ref "U6") (pin "4") (pinfunction "A3_4") (pintype "bidirectional"))
    )
    (net (code "62") (name "TRIGGER_CHIP5V") (class "Default")
      (node (ref "J4") (pin "6") (pinfunction "6_6") (pintype "passive"))
      (node (ref "U6") (pin "17") (pinfunction "B3_17") (pintype "bidirectional"))
    )
    (net (code "63") (name "TX6") (class "Default")
      (node (ref "JP2") (pin "1") (pinfunction "1_1") (pintype "passive"))
    )
    (net (code "64") (name "U1_RX") (class "Default")
      (node (ref "JP1") (pin "11") (pinfunction "11_11") (pintype "passive"))
      (node (ref "U$1") (pin "67") (pinfunction "PA8/USART1_CK/I2C3_SCL_67") (pintype "bidirectional"))
    )
    (net (code "65") (name "U1_TX") (class "Default")
      (node (ref "JP1") (pin "10") (pinfunction "10_10") (pintype "passive"))
      (node (ref "U$1") (pin "68") (pinfunction "PA9/USART1_TX/I2C3_SMBA_68") (pintype "bidirectional"))
    )
    (net (code "66") (name "U2_RX") (class "Default")
      (node (ref "JP1") (pin "9") (pinfunction "9_9") (pintype "passive"))
      (node (ref "U$1") (pin "26") (pinfunction "PA3/USART2_RX_26") (pintype "bidirectional"))
    )
    (net (code "67") (name "U2_TX") (class "Default")
      (node (ref "JP1") (pin "12") (pinfunction "12_12") (pintype "passive"))
      (node (ref "U$1") (pin "25") (pinfunction "PA2/USART2_TX_25") (pintype "bidirectional"))
    )
    (net (code "68") (name "U3_RX") (class "Default")
      (node (ref "JP1") (pin "3") (pinfunction "3_3") (pintype "passive"))
      (node (ref "U$1") (pin "48") (pinfunction "PB11/I2C2_SDA/USART3_RX_48") (pintype "bidirectional"))
    )
    (net (code "69") (name "U3_TX") (class "Default")
      (node (ref "JP1") (pin "1") (pinfunction "1_1") (pintype "passive"))
      (node (ref "U$1") (pin "47") (pinfunction "PB10/I2C2_SCL/SPI2_SCK/USART3_TX_47") (pintype "bidirectional"))
    )
    (net (code "70") (name "U4_RX") (class "Default")
      (node (ref "JP2") (pin "11") (pinfunction "11_11") (pintype "passive"))
      (node (ref "U$1") (pin "24") (pinfunction "PA1/USART2_RTS/USART4_RX_24") (pintype "bidirectional"))
    )
    (net (code "71") (name "U4_TX") (class "Default")
      (node (ref "JP2") (pin "10") (pinfunction "10_10") (pintype "passive"))
      (node (ref "U$1") (pin "23") (pinfunction "PA0/USART2_CTS/USART4_TX/WKUP_23") (pintype "bidirectional"))
    )
    (net (code "72") (name "U5_RX") (class "Default")
      (node (ref "JP2") (pin "9") (pinfunction "9_9") (pintype "passive"))
      (node (ref "U$1") (pin "83") (pinfunction "PD2/UART5_RX_83") (pintype "bidirectional"))
    )
    (net (code "73") (name "U5_TX") (class "Default")
      (node (ref "JP2") (pin "12") (pinfunction "12_12") (pintype "passive"))
      (node (ref "U$1") (pin "80") (pinfunction "PC12/UART5_TX/SPI3_MOSI/USART3_CK_80") (pintype "bidirectional"))
    )
    (net (code "74") (name "U6_RX") (class "Default")
      (node (ref "U$1") (pin "64") (pinfunction "PC7/USART6_RX_64") (pintype "bidirectional"))
      (node (ref "U$6") (pin "P$16") (pinfunction "TX_P$16") (pintype "bidirectional"))
    )
    (net (code "75") (name "U6_TX") (class "Default")
      (node (ref "U$1") (pin "63") (pinfunction "PC6/USART6_TX_63") (pintype "bidirectional"))
      (node (ref "U$6") (pin "P$15") (pinfunction "RX_P$15") (pintype "bidirectional"))
    )
    (net (code "76") (name "VDC_1") (class "Default")
      (node (ref "JP1") (pin "4") (pinfunction "4_4") (pintype "passive"))
      (node (ref "R14") (pin "1") (pinfunction "1_1") (pintype "passive"))
      (node (ref "U$4") (pin "VIN") (pinfunction "VIN_VIN") (pintype "bidirectional"))
      (node (ref "U4") (pin "2") (pinfunction "K_2") (pintype "bidirectional"))
    )
    (net (code "77") (name "VDC_2") (class "Default")
      (node (ref "JP2") (pin "4") (pinfunction "4_4") (pintype "passive"))
      (node (ref "U2") (pin "2") (pinfunction "K_2") (pintype "bidirectional"))
    )
    (net (code "78") (name "WAVEFORM") (class "Default")
      (node (ref "U6") (pin "1") (pinfunction "A1_1") (pintype "bidirectional"))
    )
    (net (code "79") (name "WAVEFORM5V") (class "Default")
      (node (ref "J4") (pin "8") (pinfunction "8_8") (pintype "passive"))
      (node (ref "U6") (pin "20") (pinfunction "B1_20") (pintype "bidirectional"))
    )
    (net (code "80") (name "unconnected-(JP1-Pad13)") (class "Default")
      (node (ref "JP1") (pin "13") (pinfunction "13_13") (pintype "passive"))
    )
    (net (code "81") (name "unconnected-(JP1-Pad14)") (class "Default")
      (node (ref "JP1") (pin "14") (pinfunction "14_14") (pintype "passive"))
    )
    (net (code "82") (name "unconnected-(JP1-Pad15)") (class "Default")
      (node (ref "JP1") (pin "15") (pinfunction "15_15") (pintype "passive"))
    )
    (net (code "83") (name "unconnected-(JP1-Pad18)") (class "Default")
      (node (ref "JP1") (pin "18") (pinfunction "18_18") (pintype "passive"))
    )
    (net (code "84") (name "unconnected-(JP1-Pad20)") (class "Default")
      (node (ref "JP1") (pin "20") (pinfunction "20_20") (pintype "passive"))
    )
    (net (code "85") (name "unconnected-(JP1-Pad21)") (class "Default")
      (node (ref "JP1") (pin "21") (pinfunction "21_21") (pintype "passive"))
    )
    (net (code "86") (name "unconnected-(JP1-Pad22)") (class "Default")
      (node (ref "JP1") (pin "22") (pinfunction "22_22") (pintype "passive"))
    )
    (net (code "87") (name "unconnected-(JP1-Pad24)") (class "Default")
      (node (ref "JP1") (pin "24") (pinfunction "24_24") (pintype "passive"))
    )
    (net (code "88") (name "unconnected-(JP1-Pad26)") (class "Default")
      (node (ref "JP1") (pin "26") (pinfunction "26_26") (pintype "passive"))
    )
    (net (code "89") (name "unconnected-(JP2-Pad13)") (class "Default")
      (node (ref "JP2") (pin "13") (pinfunction "13_13") (pintype "passive"))
    )
    (net (code "90") (name "unconnected-(JP2-Pad14)") (class "Default")
      (node (ref "JP2") (pin "14") (pinfunction "14_14") (pintype "passive"))
    )
    (net (code "91") (name "unconnected-(JP2-Pad15)") (class "Default")
      (node (ref "JP2") (pin "15") (pinfunction "15_15") (pintype "passive"))
    )
    (net (code "92") (name "unconnected-(JP2-Pad18)") (class "Default")
      (node (ref "JP2") (pin "18") (pinfunction "18_18") (pintype "passive"))
    )
    (net (code "93") (name "unconnected-(JP2-Pad20)") (class "Default")
      (node (ref "JP2") (pin "20") (pinfunction "20_20") (pintype "passive"))
    )
    (net (code "94") (name "unconnected-(JP2-Pad21)") (class "Default")
      (node (ref "JP2") (pin "21") (pinfunction "21_21") (pintype "passive"))
    )
    (net (code "95") (name "unconnected-(JP2-Pad22)") (class "Default")
      (node (ref "JP2") (pin "22") (pinfunction "22_22") (pintype "passive"))
    )
    (net (code "96") (name "unconnected-(JP2-Pad24)") (class "Default")
      (node (ref "JP2") (pin "24") (pinfunction "24_24") (pintype "passive"))
    )
    (net (code "97") (name "unconnected-(JP2-Pad26)") (class "Default")
      (node (ref "JP2") (pin "26") (pinfunction "26_26") (pintype "passive"))
    )
    (net (code "98") (name "unconnected-(JP12-6-PadP$6)") (class "Default")
      (node (ref "JP12") (pin "P$6") (pinfunction "6_P$6") (pintype "passive"))
    )
    (net (code "99") (name "unconnected-(JP12-9-PadP$9)") (class "Default")
      (node (ref "JP12") (pin "P$9") (pinfunction "9_P$9") (pintype "passive"))
    )
    (net (code "100") (name "unconnected-(JP12-10-PadP$10)") (class "Default")
      (node (ref "JP12") (pin "P$10") (pinfunction "10_P$10") (pintype "passive"))
    )
    (net (code "101") (name "unconnected-(S2A-O-Pad1)") (class "Default")
      (node (ref "S2") (pin "1") (pinfunction "O_1") (pintype "passive"))
    )
    (net (code "102") (name "unconnected-(S2B-O-Pad4)") (class "Default")
      (node (ref "S2") (pin "4") (pinfunction "O_4") (pintype "passive"))
    )
    (net (code "103") (name "unconnected-(U$1A-PC0-Pad15)") (class "Default")
      (node (ref "U$1") (pin "15") (pinfunction "PC0_15") (pintype "bidirectional"))
    )
    (net (code "104") (name "unconnected-(U$1A-PC1-Pad16)") (class "Default")
      (node (ref "U$1") (pin "16") (pinfunction "PC1_16") (pintype "bidirectional"))
    )
    (net (code "105") (name "unconnected-(U$1A-PC2{slash}SPI2_MISO-Pad17)") (class "Default")
      (node (ref "U$1") (pin "17") (pinfunction "PC2/SPI2_MISO_17") (pintype "bidirectional"))
    )
    (net (code "106") (name "unconnected-(U$1A-PC3{slash}SPI2_MOSI-Pad18)") (class "Default")
      (node (ref "U$1") (pin "18") (pinfunction "PC3/SPI2_MOSI_18") (pintype "bidirectional"))
    )
    (net (code "107") (name "unconnected-(U$1A-PC13{slash}RTC_AF1-Pad7)") (class "Default")
      (node (ref "U$1") (pin "7") (pinfunction "PC13/RTC_AF1_7") (pintype "bidirectional"))
    )
    (net (code "108") (name "unconnected-(U$1A-PC14{slash}OSC32_IN-Pad8)") (class "Default")
      (node (ref "U$1") (pin "8") (pinfunction "PC14/OSC32_IN_8") (pintype "bidirectional"))
    )
    (net (code "109") (name "unconnected-(U$1A-PC15{slash}OSC32_OUT-Pad9)") (class "Default")
      (node (ref "U$1") (pin "9") (pinfunction "PC15/OSC32_OUT_9") (pintype "bidirectional"))
    )
    (net (code "110") (name "unconnected-(U$1A-PE2-Pad1)") (class "Default")
      (node (ref "U$1") (pin "1") (pinfunction "PE2_1") (pintype "bidirectional"))
    )
    (net (code "111") (name "unconnected-(U$1A-PE3-Pad2)") (class "Default")
      (node (ref "U$1") (pin "2") (pinfunction "PE3_2") (pintype "bidirectional"))
    )
    (net (code "112") (name "unconnected-(U$1A-PE4-Pad3)") (class "Default")
      (node (ref "U$1") (pin "3") (pinfunction "PE4_3") (pintype "bidirectional"))
    )
    (net (code "113") (name "unconnected-(U$1A-PE5-Pad4)") (class "Default")
      (node (ref "U$1") (pin "4") (pinfunction "PE5_4") (pintype "bidirectional"))
    )
    (net (code "114") (name "unconnected-(U$1A-PE6-Pad5)") (class "Default")
      (node (ref "U$1") (pin "5") (pinfunction "PE6_5") (pintype "bidirectional"))
    )
    (net (code "115") (name "unconnected-(U$1B-PA4{slash}SPI1_NSS{slash}SPI3_NSS{slash}USART2_CK-Pad29)") (class "Default")
      (node (ref "U$1") (pin "29") (pinfunction "PA4/SPI1_NSS/SPI3_NSS/USART2_CK_29") (pintype "bidirectional"))
    )
    (net (code "116") (name "unconnected-(U$1B-PA5{slash}SPI1_SCK-Pad30)") (class "Default")
      (node (ref "U$1") (pin "30") (pinfunction "PA5/SPI1_SCK_30") (pintype "bidirectional"))
    )
    (net (code "117") (name "unconnected-(U$1B-PA6{slash}SPI1_MISO-Pad31)") (class "Default")
      (node (ref "U$1") (pin "31") (pinfunction "PA6/SPI1_MISO_31") (pintype "bidirectional"))
    )
    (net (code "118") (name "unconnected-(U$1B-PA7{slash}SPI1_MOSI-Pad32)") (class "Default")
      (node (ref "U$1") (pin "32") (pinfunction "PA7/SPI1_MOSI_32") (pintype "bidirectional"))
    )
    (net (code "119") (name "unconnected-(U$1B-PB1-Pad36)") (class "Default")
      (node (ref "U$1") (pin "36") (pinfunction "PB1_36") (pintype "bidirectional"))
    )
    (net (code "120") (name "unconnected-(U$1B-PB2{slash}BOOT1-Pad37)") (class "Default")
      (node (ref "U$1") (pin "37") (pinfunction "PB2/BOOT1_37") (pintype "bidirectional"))
    )
    (net (code "121") (name "unconnected-(U$1B-PE15-Pad46)") (class "Default")
      (node (ref "U$1") (pin "46") (pinfunction "PE15_46") (pintype "bidirectional"))
    )
    (net (code "122") (name "unconnected-(U$1C-PA10{slash}USART1_RX-Pad69)") (class "Default")
      (node (ref "U$1") (pin "69") (pinfunction "PA10/USART1_RX_69") (pintype "bidirectional"))
    )
    (net (code "123") (name "unconnected-(U$1C-PA11{slash}USART1_CTS{slash}CAN1_RX{slash}OTG_FS_D--Pad70)") (class "Default")
      (node (ref "U$1") (pin "70") (pinfunction "PA11/USART1_CTS/CAN1_RX/OTG_FS_D-_70") (pintype "bidirectional"))
    )
    (net (code "124") (name "unconnected-(U$1C-PA12{slash}USART1_RTS{slash}CAN1_TX{slash}OTG_FS_DP+-Pad71)") (class "Default")
      (node (ref "U$1") (pin "71") (pinfunction "PA12/USART1_RTS/CAN1_TX/OTG_FS_DP+_71") (pintype "bidirectional"))
    )
    (net (code "125") (name "unconnected-(U$1C-PB12{slash}SPI2_NSS{slash}I2C2_SMBA{slash}USART3_CK{slash}CAN2_RX-Pad51)") (class "Default")
      (node (ref "U$1") (pin "51") (pinfunction "PB12/SPI2_NSS/I2C2_SMBA/USART3_CK/CAN2_RX_51") (pintype "bidirectional"))
    )
    (net (code "126") (name "unconnected-(U$1C-PC8{slash}USART6_CK-Pad65)") (class "Default")
      (node (ref "U$1") (pin "65") (pinfunction "PC8/USART6_CK_65") (pintype "bidirectional"))
    )
    (net (code "127") (name "unconnected-(U$1C-PC9{slash}I2C3_SDA-Pad66)") (class "Default")
      (node (ref "U$1") (pin "66") (pinfunction "PC9/I2C3_SDA_66") (pintype "bidirectional"))
    )
    (net (code "128") (name "unconnected-(U$1C-PD9{slash}USART3_RX-Pad56)") (class "Default")
      (node (ref "U$1") (pin "56") (pinfunction "PD9/USART3_RX_56") (pintype "bidirectional"))
    )
    (net (code "129") (name "unconnected-(U$1C-PD10{slash}USART3_CK-Pad57)") (class "Default")
      (node (ref "U$1") (pin "57") (pinfunction "PD10/USART3_CK_57") (pintype "bidirectional"))
    )
    (net (code "130") (name "unconnected-(U$1C-PD11{slash}USART3_CTS-Pad58)") (class "Default")
      (node (ref "U$1") (pin "58") (pinfunction "PD11/USART3_CTS_58") (pintype "bidirectional"))
    )
    (net (code "131") (name "unconnected-(U$1C-PD12{slash}USART3_RTS-Pad59)") (class "Default")
      (node (ref "U$1") (pin "59") (pinfunction "PD12/USART3_RTS_59") (pintype "bidirectional"))
    )
    (net (code "132") (name "unconnected-(U$1C-PD13-Pad60)") (class "Default")
      (node (ref "U$1") (pin "60") (pinfunction "PD13_60") (pintype "bidirectional"))
    )
    (net (code "133") (name "unconnected-(U$1C-PD14-Pad61)") (class "Default")
      (node (ref "U$1") (pin "61") (pinfunction "PD14_61") (pintype "bidirectional"))
    )
    (net (code "134") (name "unconnected-(U$1C-PD15-Pad62)") (class "Default")
      (node (ref "U$1") (pin "62") (pinfunction "PD15_62") (pintype "bidirectional"))
    )
    (net (code "135") (name "unconnected-(U$1D-PA15{slash}JTDI{slash}SPI3_NSS{slash}SPI1_NSS-Pad77)") (class "Default")
      (node (ref "U$1") (pin "77") (pinfunction "PA15/JTDI/SPI3_NSS/SPI1_NSS_77") (pintype "bidirectional"))
    )
    (net (code "136") (name "unconnected-(U$1D-PB8{slash}I2C1_SCL{slash}CAN1_RX-Pad95)") (class "Default")
      (node (ref "U$1") (pin "95") (pinfunction "PB8/I2C1_SCL/CAN1_RX_95") (pintype "bidirectional"))
    )
    (net (code "137") (name "unconnected-(U$1D-PB9{slash}I2C1_SDA{slash}SPI2_NSS{slash}CAN1_TX-Pad96)") (class "Default")
      (node (ref "U$1") (pin "96") (pinfunction "PB9/I2C1_SDA/SPI2_NSS/CAN1_TX_96") (pintype "bidirectional"))
    )
    (net (code "138") (name "unconnected-(U$1D-PC10{slash}SPI3_SCK{slash}UART4_TX{slash}USART3_CK-Pad78)") (class "Default")
      (node (ref "U$1") (pin "78") (pinfunction "PC10/SPI3_SCK/UART4_TX/USART3_CK_78") (pintype "bidirectional"))
    )
    (net (code "139") (name "unconnected-(U$1D-PC11{slash}UART4_RX{slash}SPI3_MISO{slash}USART3_RX-Pad79)") (class "Default")
      (node (ref "U$1") (pin "79") (pinfunction "PC11/UART4_RX/SPI3_MISO/USART3_RX_79") (pintype "bidirectional"))
    )
    (net (code "140") (name "unconnected-(U$1D-PD0{slash}CAN1_RX-Pad81)") (class "Default")
      (node (ref "U$1") (pin "81") (pinfunction "PD0/CAN1_RX_81") (pintype "bidirectional"))
    )
    (net (code "141") (name "unconnected-(U$1D-PD1{slash}CAN1_TX-Pad82)") (class "Default")
      (node (ref "U$1") (pin "82") (pinfunction "PD1/CAN1_TX_82") (pintype "bidirectional"))
    )
    (net (code "142") (name "unconnected-(U$1D-PD3{slash}USART2_CTS-Pad84)") (class "Default")
      (node (ref "U$1") (pin "84") (pinfunction "PD3/USART2_CTS_84") (pintype "bidirectional"))
    )
    (net (code "143") (name "unconnected-(U$1D-PD4{slash}USART2_RTS-Pad85)") (class "Default")
      (node (ref "U$1") (pin "85") (pinfunction "PD4/USART2_RTS_85") (pintype "bidirectional"))
    )
    (net (code "144") (name "unconnected-(U$1D-PD5{slash}USART2_TX-Pad86)") (class "Default")
      (node (ref "U$1") (pin "86") (pinfunction "PD5/USART2_TX_86") (pintype "bidirectional"))
    )
    (net (code "145") (name "unconnected-(U$1D-PD6{slash}USART2_RX-Pad87)") (class "Default")
      (node (ref "U$1") (pin "87") (pinfunction "PD6/USART2_RX_87") (pintype "bidirectional"))
    )
    (net (code "146") (name "unconnected-(U$1D-PE0-Pad97)") (class "Default")
      (node (ref "U$1") (pin "97") (pinfunction "PE0_97") (pintype "bidirectional"))
    )
    (net (code "147") (name "unconnected-(U$1D-PE1-Pad98)") (class "Default")
      (node (ref "U$1") (pin "98") (pinfunction "PE1_98") (pintype "bidirectional"))
    )
    (net (code "148") (name "unconnected-(U$2-PadNC)") (class "Default")
      (node (ref "U$2") (pin "NC") (pinfunction "NC_NC") (pintype "bidirectional"))
    )
    (net (code "149") (name "unconnected-(U$6-CLK-PadP$1)") (class "Default")
      (node (ref "U$6") (pin "P$1") (pinfunction "CLK_P$1") (pintype "bidirectional"))
    )
    (net (code "150") (name "unconnected-(U$6-P0-PadP$6)") (class "Default")
      (node (ref "U$6") (pin "P$6") (pinfunction "P0_P$6") (pintype "bidirectional"))
    )
    (net (code "151") (name "unconnected-(U$6-P1-PadP$7)") (class "Default")
      (node (ref "U$6") (pin "P$7") (pinfunction "P1_P$7") (pintype "bidirectional"))
    )
    (net (code "152") (name "unconnected-(U$6-P2-PadP$5)") (class "Default")
      (node (ref "U$6") (pin "P$5") (pinfunction "P2_P$5") (pintype "bidirectional"))
    )
    (net (code "153") (name "unconnected-(U$6-P5-PadP$10)") (class "Default")
      (node (ref "U$6") (pin "P$10") (pinfunction "P5_P$10") (pintype "bidirectional"))
    )
    (net (code "154") (name "unconnected-(U$6-P12-PadP$26)") (class "Default")
      (node (ref "U$6") (pin "P$26") (pinfunction "P12_P$26") (pintype "bidirectional"))
    )
    (net (code "155") (name "unconnected-(U$6-P13-PadP$24)") (class "Default")
      (node (ref "U$6") (pin "P$24") (pinfunction "P13_P$24") (pintype "bidirectional"))
    )
    (net (code "156") (name "unconnected-(U$6-P14-PadP$27)") (class "Default")
      (node (ref "U$6") (pin "P$27") (pinfunction "P14_P$27") (pintype "bidirectional"))
    )
    (net (code "157") (name "unconnected-(U$6-P15-PadP$4)") (class "Default")
      (node (ref "U$6") (pin "P$4") (pinfunction "P15_P$4") (pintype "bidirectional"))
    )
    (net (code "158") (name "unconnected-(U$6-P18-PadP$11)") (class "Default")
      (node (ref "U$6") (pin "P$11") (pinfunction "P18_P$11") (pintype "bidirectional"))
    )
    (net (code "159") (name "unconnected-(U$6-P19-PadP$12)") (class "Default")
      (node (ref "U$6") (pin "P$12") (pinfunction "P19_P$12") (pintype "bidirectional"))
    )
    (net (code "160") (name "unconnected-(U$6-P21-PadP$14)") (class "Default")
      (node (ref "U$6") (pin "P$14") (pinfunction "P21_P$14") (pintype "bidirectional"))
    )
    (net (code "161") (name "unconnected-(U$6-P22-PadP$17)") (class "Default")
      (node (ref "U$6") (pin "P$17") (pinfunction "P22_P$17") (pintype "bidirectional"))
    )
    (net (code "162") (name "unconnected-(U$6-P23-PadP$18)") (class "Default")
      (node (ref "U$6") (pin "P$18") (pinfunction "P23_P$18") (pintype "bidirectional"))
    )
    (net (code "163") (name "unconnected-(U$6-P25-PadP$30)") (class "Default")
      (node (ref "U$6") (pin "P$30") (pinfunction "P25_P$30") (pintype "bidirectional"))
    )
    (net (code "164") (name "unconnected-(U$6-P26-PadP$29)") (class "Default")
      (node (ref "U$6") (pin "P$29") (pinfunction "P26_P$29") (pintype "bidirectional"))
    )
    (net (code "165") (name "unconnected-(U$6-P27-PadP$28)") (class "Default")
      (node (ref "U$6") (pin "P$28") (pinfunction "P27_P$28") (pintype "bidirectional"))
    )
    (net (code "166") (name "unconnected-(U$6-P32-PadP$32)") (class "Default")
      (node (ref "U$6") (pin "P$32") (pinfunction "P32_P$32") (pintype "bidirectional"))
    )
    (net (code "167") (name "unconnected-(U$6-P33-PadP$31)") (class "Default")
      (node (ref "U$6") (pin "P$31") (pinfunction "P33_P$31") (pintype "bidirectional"))
    )
    (net (code "168") (name "unconnected-(U$6-P34-PadP$34)") (class "Default")
      (node (ref "U$6") (pin "P$34") (pinfunction "P34_P$34") (pintype "bidirectional"))
    )
    (net (code "169") (name "unconnected-(U$6-P35-PadP$33)") (class "Default")
      (node (ref "U$6") (pin "P$33") (pinfunction "P35_P$33") (pintype "bidirectional"))
    )
    (net (code "170") (name "unconnected-(U$6-SD0-PadP$2)") (class "Default")
      (node (ref "U$6") (pin "P$2") (pinfunction "SD0_P$2") (pintype "bidirectional"))
    )
    (net (code "171") (name "unconnected-(U$6-SD1-PadP$3)") (class "Default")
      (node (ref "U$6") (pin "P$3") (pinfunction "SD1_P$3") (pintype "bidirectional"))
    )
    (net (code "172") (name "unconnected-(U$6-SD2-PadP$23)") (class "Default")
      (node (ref "U$6") (pin "P$23") (pinfunction "SD2_P$23") (pintype "bidirectional"))
    )
    (net (code "173") (name "unconnected-(U$6-SD3-PadP$22)") (class "Default")
      (node (ref "U$6") (pin "P$22") (pinfunction "SD3_P$22") (pintype "bidirectional"))
    )
    (net (code "174") (name "unconnected-(U$6-SVN-PadP$35)") (class "Default")
      (node (ref "U$6") (pin "P$35") (pinfunction "SVN_P$35") (pintype "bidirectional"))
    )
    (net (code "175") (name "unconnected-(U$6-SVP-PadP$36)") (class "Default")
      (node (ref "U$6") (pin "P$36") (pinfunction "SVP_P$36") (pintype "bidirectional"))
    )
    (net (code "176") (name "unconnected-(U6-OE-Pad10)") (class "Default")
      (node (ref "U6") (pin "10") (pinfunction "OE_10") (pintype "bidirectional"))
    )
  )
)
